# JTAG.net
KiCad netlist of a schematic drawn in Altium Designer
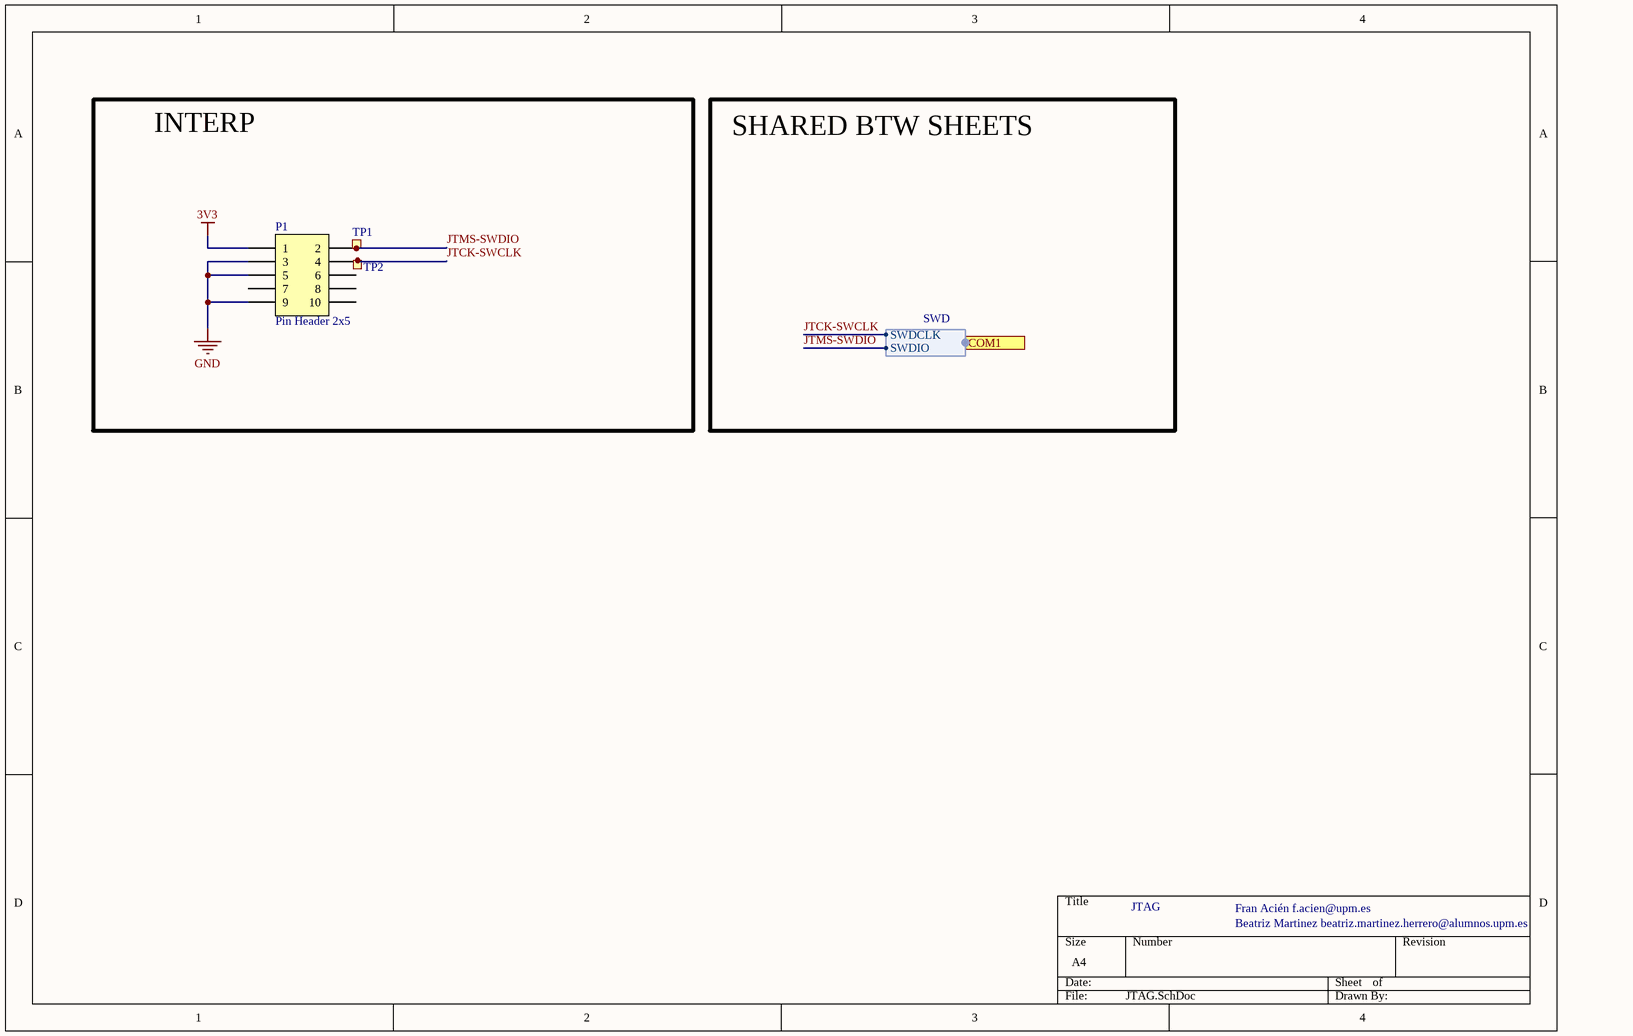
[diagram p0: JTAG.SchDoc]

(export (version "E")
  (design (tool "Eeschema 10.0.6"))
  (components
    (comp (ref "P1")
      (value "Pin Header 2x5")
      (footprint "HDR_2x5-SMD-1.27mm-ANG")
      (description "Pin Header 2x5, 1.27mm (50mil)")
      (fields
        (field (name "PART NUMBER") "Pin Header 2x5 SMD, 1.27mm, Angled")
        (field (name "MANUFACTURER") "Samtec")
        (field (name "PUBLISHER") "Nordic Semiconductor")
      )
      (libsource (lib "FEEL2020") (part "Pin Header 2x5 SMD, 1.27mm, Angled"))
    )
    (comp (ref "TP1")
      (value "Ø1.0mm,SMD")
      (footprint "TP_SMD_Ø1.0mm")
      (description "1.0mm circular SMD testpad")
      (fields
        (field (name "PART NUMBER") "TP_SMD_Ø1.0MM")
        (field (name "MANUFACTURER") "Nordic Semiconductor")
        (field (name "PUBLISHER") "Nordic Semiconductor")
      )
      (libsource (lib "") (part "TP_SMD_Ø1.0MM_1"))
    )
    (comp (ref "TP2")
      (value "Ø1.0mm,SMD")
      (footprint "TP_SMD_Ø1.0mm")
      (description "1.0mm circular SMD testpad")
      (fields
        (field (name "PART NUMBER") "TP_SMD_Ø1.0MM")
        (field (name "MANUFACTURER") "Nordic Semiconductor")
        (field (name "PUBLISHER") "Nordic Semiconductor")
      )
      (libsource (lib "FEEL2020") (part "TP_SMD_Ø1.0MM"))
    )
  )
  (nets
    (net (code "2") (name "/JTCK-SWCLK") (class "Default")
      (node (ref "P1") (pin "4") (pinfunction "4_4") (pintype "passive"))
      (node (ref "TP2") (pin "1") (pinfunction "1_1") (pintype "passive"))
    )
    (net (code "3") (name "/JTMS-SWDIO") (class "Default")
      (node (ref "P1") (pin "2") (pinfunction "2_2") (pintype "passive"))
      (node (ref "TP1") (pin "1") (pinfunction "1_1") (pintype "passive"))
    )
    (net (code "5") (name "3V3") (class "Default")
      (node (ref "P1") (pin "1") (pinfunction "1_1") (pintype "passive"))
    )
    (net (code "6") (name "GND") (class "Default")
      (node (ref "P1") (pin "3") (pinfunction "3_3") (pintype "passive"))
      (node (ref "P1") (pin "5") (pinfunction "5_5") (pintype "passive"))
      (node (ref "P1") (pin "9") (pinfunction "9_9") (pintype "passive"))
    )
    (net (code "7") (name "unconnected-(P1-Pad6)") (class "Default")
      (node (ref "P1") (pin "6") (pinfunction "6_6") (pintype "passive"))
    )
    (net (code "8") (name "unconnected-(P1-Pad7)") (class "Default")
      (node (ref "P1") (pin "7") (pinfunction "7_7") (pintype "passive"))
    )
    (net (code "9") (name "unconnected-(P1-Pad8)") (class "Default")
      (node (ref "P1") (pin "8") (pinfunction "8_8") (pintype "passive"))
    )
    (net (code "10") (name "unconnected-(P1-Pad10)") (class "Default")
      (node (ref "P1") (pin "10") (pinfunction "10_10") (pintype "passive"))
    )
  )
)
